# Dev_dsPIC_DIP.net
KiCad netlist of a schematic drawn in EAGLE
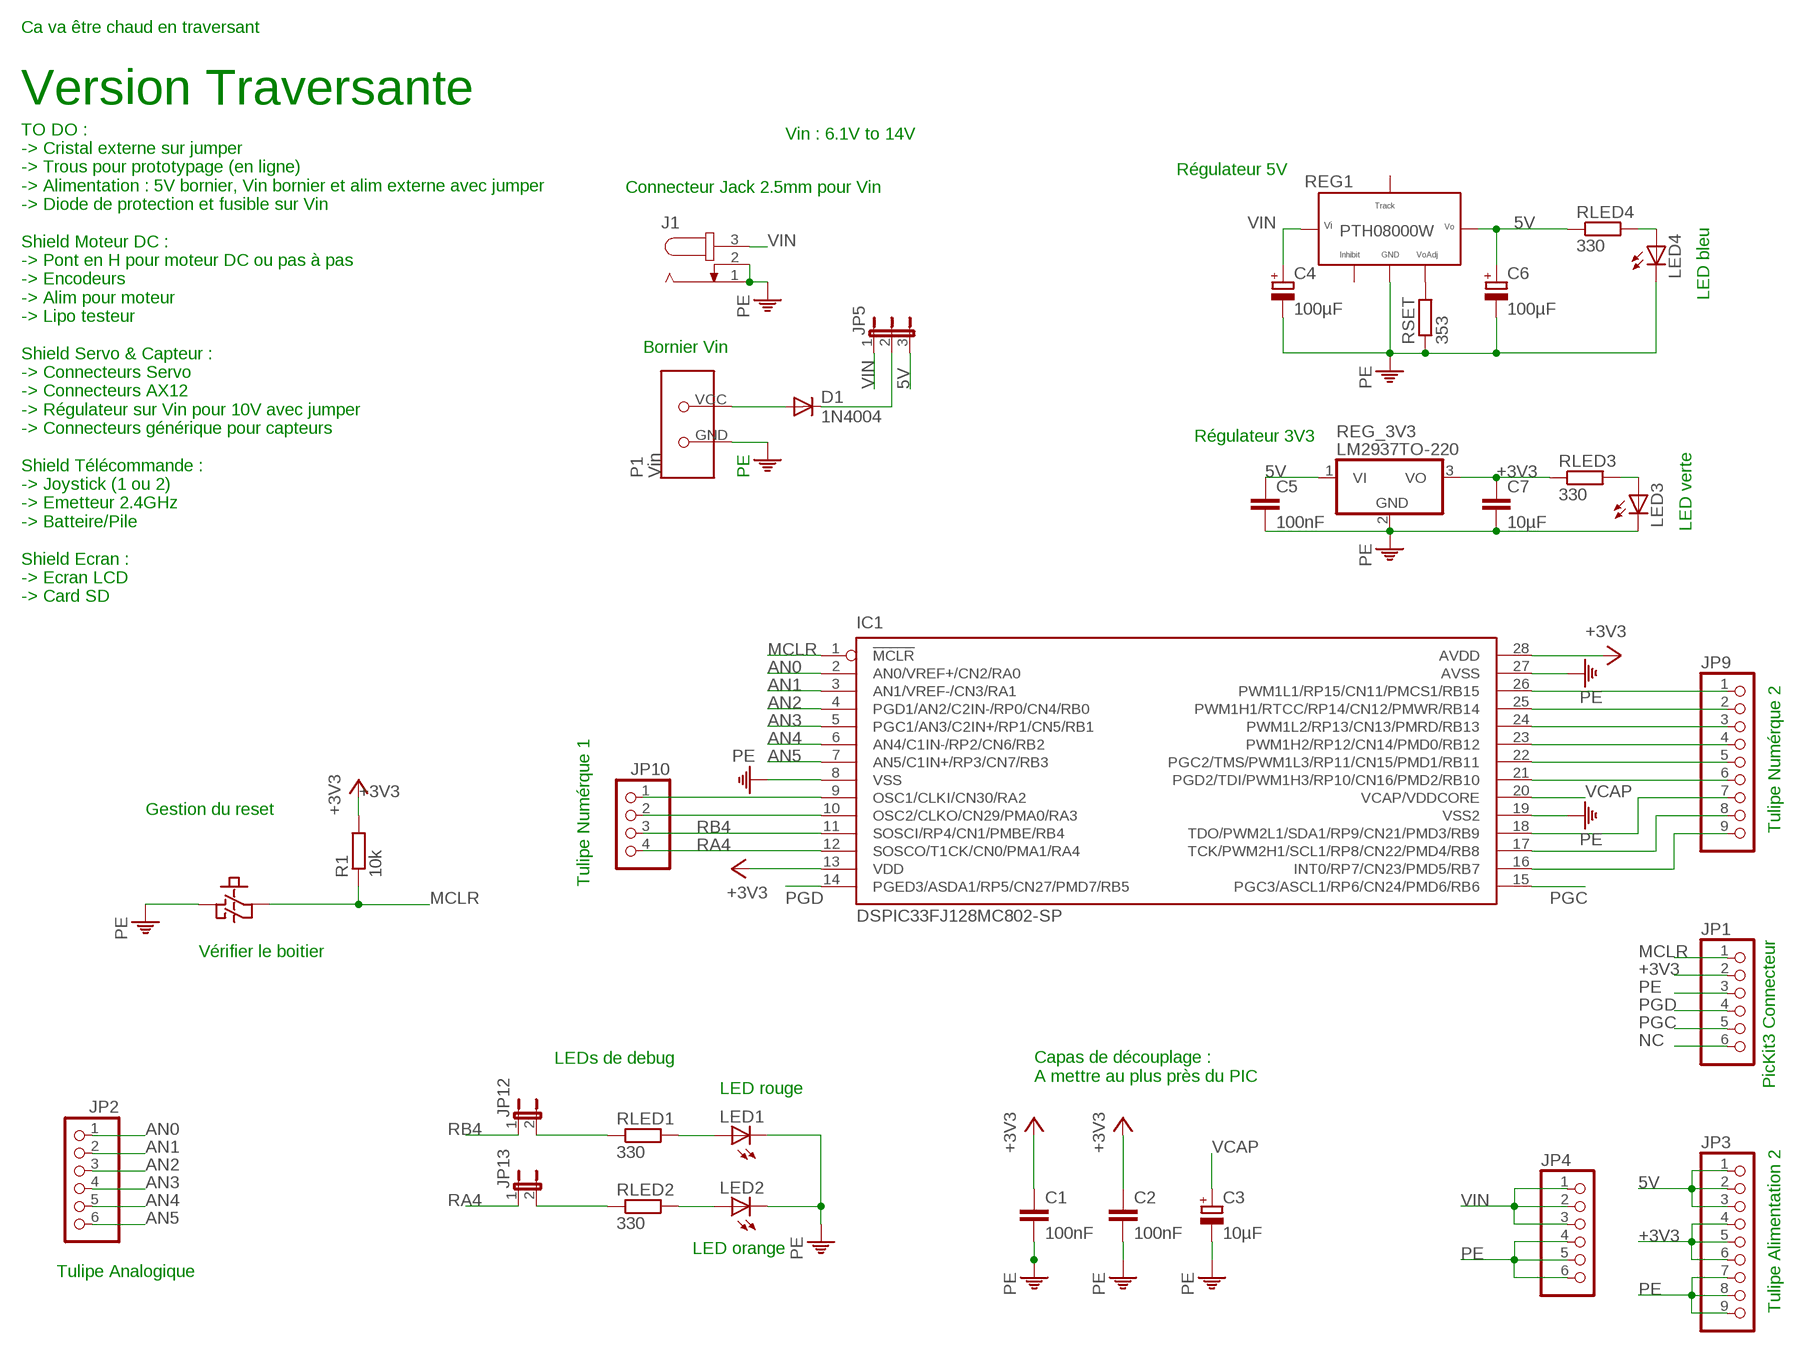
[diagram p0: schematic, sheet 1]

(export (version "E")
  (design (tool "Eeschema 10.0.6"))
  (components
    (comp (ref "C1")
      (value "100nF")
      (footprint "eagle-import:C050-035X075")
      (libsource (lib "eagle-import") (part "C-EU050-035X075"))
    )
    (comp (ref "C2")
      (value "100nF")
      (footprint "eagle-import:C050-035X075")
      (libsource (lib "eagle-import") (part "C-EU050-035X075"))
    )
    (comp (ref "C3")
      (value "10µF")
      (footprint "eagle-import:E2,5-4R")
      (libsource (lib "eagle-import") (part "CPOL-EUE2.5-5V"))
    )
    (comp (ref "C4")
      (value "100µF")
      (footprint "eagle-import:E3,5-8")
      (libsource (lib "eagle-import") (part "CPOL-EUE3.5-8"))
    )
    (comp (ref "C5")
      (value "100nF")
      (footprint "eagle-import:C050-035X075")
      (libsource (lib "eagle-import") (part "C-EU050-035X075"))
    )
    (comp (ref "C6")
      (value "100µF")
      (footprint "eagle-import:E3,5-8")
      (libsource (lib "eagle-import") (part "CPOL-EUE3.5-8"))
    )
    (comp (ref "C7")
      (value "10µF")
      (footprint "eagle-import:C050-035X075")
      (libsource (lib "eagle-import") (part "C-EU050-035X075"))
    )
    (comp (ref "D1")
      (value "1N4004")
      (footprint "eagle-import:DO41-10")
      (libsource (lib "eagle-import") (part "1N4004"))
    )
    (comp (ref "IC1")
      (value "DSPIC33FJ128MC802-SP")
      (footprint "eagle-import:DIL28-3")
      (libsource (lib "eagle-import") (part "DSPIC33FJ128MC802-SP"))
    )
    (comp (ref "J1")
      (value "JACK-PLUG1")
      (footprint "eagle-import:SPC4078")
      (libsource (lib "eagle-import") (part "JACK-PLUG1"))
    )
    (comp (ref "JP1")
      (value "PINHD-1X6/90")
      (footprint "eagle-import:1X06_90")
      (libsource (lib "eagle-import") (part "PINHD-1X6/90"))
    )
    (comp (ref "JP2")
      (value "PINHD-1X6")
      (footprint "eagle-import:1X06")
      (libsource (lib "eagle-import") (part "PINHD-1X6"))
    )
    (comp (ref "JP3")
      (value "PINHD-1X9")
      (footprint "eagle-import:1X09")
      (libsource (lib "eagle-import") (part "PINHD-1X9"))
    )
    (comp (ref "JP4")
      (value "PINHD-1X6")
      (footprint "eagle-import:1X06")
      (libsource (lib "eagle-import") (part "PINHD-1X6"))
    )
    (comp (ref "JP5")
      (value "JP2E")
      (footprint "eagle-import:JP2")
      (libsource (lib "eagle-import") (part "JP2E"))
    )
    (comp (ref "JP9")
      (value "PINHD-1X9")
      (footprint "eagle-import:1X09")
      (libsource (lib "eagle-import") (part "PINHD-1X9"))
    )
    (comp (ref "JP10")
      (value "PINHD-1X4")
      (footprint "eagle-import:1X04")
      (libsource (lib "eagle-import") (part "PINHD-1X4"))
    )
    (comp (ref "JP12")
      (value "JP1E")
      (footprint "eagle-import:JP1")
      (libsource (lib "eagle-import") (part "JP1E"))
    )
    (comp (ref "JP13")
      (value "JP1E")
      (footprint "eagle-import:JP1")
      (libsource (lib "eagle-import") (part "JP1E"))
    )
    (comp (ref "LED1")
      (value "LED3MM")
      (footprint "eagle-import:LED3MM")
      (libsource (lib "eagle-import") (part "LED3MM"))
    )
    (comp (ref "LED2")
      (value "LED3MM")
      (footprint "eagle-import:LED3MM")
      (libsource (lib "eagle-import") (part "LED3MM"))
    )
    (comp (ref "LED3")
      (value "LED3MM")
      (footprint "eagle-import:LED3MM")
      (libsource (lib "eagle-import") (part "LED3MM"))
    )
    (comp (ref "LED4")
      (value "LED3MM")
      (footprint "eagle-import:LED3MM")
      (libsource (lib "eagle-import") (part "LED3MM"))
    )
    (comp (ref "P1")
      (value "Vin")
      (footprint "eagle-import:BORNIER_COUDEE_3.5")
      (libsource (lib "eagle-import") (part "BORNIER_3.5MM"))
    )
    (comp (ref "R1")
      (value "10k")
      (footprint "eagle-import:RES_DIP_PERSO")
      (libsource (lib "eagle-import") (part "RES_PERSO"))
    )
    (comp (ref "REG1")
      (value "PTH08000W(EUS)")
      (footprint "eagle-import:TRHOUGH_HOLE_(EUS)")
      (libsource (lib "eagle-import") (part "PTH08000W(EUS)"))
    )
    (comp (ref "REG_3V3")
      (value "LM2937TO-220")
      (footprint "eagle-import:TO220V")
      (libsource (lib "eagle-import") (part "LM2937TO-220"))
    )
    (comp (ref "RLED1")
      (value "330")
      (footprint "eagle-import:RES_DIP_PERSO")
      (libsource (lib "eagle-import") (part "RES_PERSO"))
    )
    (comp (ref "RLED2")
      (value "330")
      (footprint "eagle-import:RES_DIP_PERSO")
      (libsource (lib "eagle-import") (part "RES_PERSO"))
    )
    (comp (ref "RLED3")
      (value "330")
      (footprint "eagle-import:RES_DIP_PERSO")
      (libsource (lib "eagle-import") (part "RES_PERSO"))
    )
    (comp (ref "RLED4")
      (value "330")
      (footprint "eagle-import:RES_DIP_PERSO")
      (libsource (lib "eagle-import") (part "RES_PERSO"))
    )
    (comp (ref "RSET")
      (value "353")
      (footprint "eagle-import:RES_DIP_PERSO")
      (libsource (lib "eagle-import") (part "RES_PERSO"))
    )
    (comp (ref "U$1") (value "BP") (footprint "eagle-import:BP") (libsource (lib "eagle-import") (part "BP")))
  )
  (nets
    (net (code "1") (name "+3V3") (class "Default")
      (node (ref "C1") (pin "1") (pinfunction "1_1") (pintype "passive"))
      (node (ref "C2") (pin "1") (pinfunction "1_1") (pintype "passive"))
      (node (ref "C7") (pin "1") (pinfunction "1_1") (pintype "passive"))
      (node (ref "IC1") (pin "13") (pinfunction "VDD_13") (pintype "power_in"))
      (node (ref "IC1") (pin "28") (pinfunction "AVDD_28") (pintype "power_in"))
      (node (ref "JP1") (pin "2") (pinfunction "2_2") (pintype "passive"))
      (node (ref "JP3") (pin "4") (pinfunction "4_4") (pintype "passive"))
      (node (ref "JP3") (pin "5") (pinfunction "5_5") (pintype "passive"))
      (node (ref "JP3") (pin "6") (pinfunction "6_6") (pintype "passive"))
      (node (ref "R1") (pin "2") (pinfunction "2_2") (pintype "passive"))
      (node (ref "REG_3V3") (pin "3") (pinfunction "VO_3") (pintype "passive"))
      (node (ref "RLED3") (pin "1") (pinfunction "1_1") (pintype "passive"))
    )
    (net (code "2") (name "/5V") (class "Default")
      (node (ref "C5") (pin "1") (pinfunction "1_1") (pintype "passive"))
      (node (ref "C6") (pin "+") (pinfunction "+_+") (pintype "passive"))
      (node (ref "JP3") (pin "1") (pinfunction "1_1") (pintype "passive"))
      (node (ref "JP3") (pin "2") (pinfunction "2_2") (pintype "passive"))
      (node (ref "JP3") (pin "3") (pinfunction "3_3") (pintype "passive"))
      (node (ref "JP5") (pin "3") (pinfunction "3_3") (pintype "passive"))
      (node (ref "REG1") (pin "6") (pinfunction "6_6") (pintype "bidirectional"))
      (node (ref "REG_3V3") (pin "1") (pinfunction "VI_1") (pintype "input"))
      (node (ref "RLED4") (pin "1") (pinfunction "1_1") (pintype "passive"))
    )
    (net (code "3") (name "/AN0") (class "Default")
      (node (ref "IC1") (pin "2") (pinfunction "AN0/VREF+/CN2/RA0_2") (pintype "bidirectional"))
      (node (ref "JP2") (pin "1") (pinfunction "1_1") (pintype "passive"))
    )
    (net (code "4") (name "/AN1") (class "Default")
      (node (ref "IC1") (pin "3") (pinfunction "AN1/VREF-/CN3/RA1_3") (pintype "bidirectional"))
      (node (ref "JP2") (pin "2") (pinfunction "2_2") (pintype "passive"))
    )
    (net (code "5") (name "/AN2") (class "Default")
      (node (ref "IC1") (pin "4") (pinfunction "PGD1/AN2/C2IN-/RP0/CN4/RB0_4") (pintype "bidirectional"))
      (node (ref "JP2") (pin "3") (pinfunction "3_3") (pintype "passive"))
    )
    (net (code "6") (name "/AN3") (class "Default")
      (node (ref "IC1") (pin "5") (pinfunction "PGC1/AN3/C2IN+/RP1/CN5/RB1_5") (pintype "bidirectional"))
      (node (ref "JP2") (pin "4") (pinfunction "4_4") (pintype "passive"))
    )
    (net (code "7") (name "/AN4") (class "Default")
      (node (ref "IC1") (pin "6") (pinfunction "AN4/C1IN-/RP2/CN6/RB2_6") (pintype "bidirectional"))
      (node (ref "JP2") (pin "5") (pinfunction "5_5") (pintype "passive"))
    )
    (net (code "8") (name "/AN5") (class "Default")
      (node (ref "IC1") (pin "7") (pinfunction "AN5/C1IN+/RP3/CN7/RB3_7") (pintype "bidirectional"))
      (node (ref "JP2") (pin "6") (pinfunction "6_6") (pintype "passive"))
    )
    (net (code "9") (name "/MCLR") (class "Default")
      (node (ref "IC1") (pin "1") (pinfunction "~{MCLR}_1") (pintype "input"))
      (node (ref "JP1") (pin "1") (pinfunction "1_1") (pintype "passive"))
      (node (ref "R1") (pin "1") (pinfunction "1_1") (pintype "passive"))
      (node (ref "U$1") (pin "3") (pinfunction "3_3") (pintype "bidirectional"))
      (node (ref "U$1") (pin "4") (pinfunction "3_4") (pintype "bidirectional"))
    )
    (net (code "10") (name "/NC") (class "Default")
      (node (ref "JP1") (pin "6") (pinfunction "6_6") (pintype "passive"))
    )
    (net (code "11") (name "/PGC") (class "Default")
      (node (ref "IC1") (pin "15") (pinfunction "PGC3/ASCL1/RP6/CN24/PMD6/RB6_15") (pintype "bidirectional"))
      (node (ref "JP1") (pin "5") (pinfunction "5_5") (pintype "passive"))
    )
    (net (code "12") (name "/PGD") (class "Default")
      (node (ref "IC1") (pin "14") (pinfunction "PGED3/ASDA1/RP5/CN27/PMD7/RB5_14") (pintype "bidirectional"))
      (node (ref "JP1") (pin "4") (pinfunction "4_4") (pintype "passive"))
    )
    (net (code "13") (name "/RA4") (class "Default")
      (node (ref "IC1") (pin "12") (pinfunction "SOSCO/T1CK/CN0/PMA1/RA4_12") (pintype "bidirectional"))
      (node (ref "JP10") (pin "4") (pinfunction "4_4") (pintype "passive"))
      (node (ref "JP13") (pin "1") (pinfunction "1_1") (pintype "passive"))
    )
    (net (code "14") (name "/RB4") (class "Default")
      (node (ref "IC1") (pin "11") (pinfunction "SOSCI/RP4/CN1/PMBE/RB4_11") (pintype "bidirectional"))
      (node (ref "JP10") (pin "3") (pinfunction "3_3") (pintype "passive"))
      (node (ref "JP12") (pin "1") (pinfunction "1_1") (pintype "passive"))
    )
    (net (code "15") (name "/VCAP") (class "Default")
      (node (ref "C3") (pin "+") (pinfunction "+_+") (pintype "passive"))
      (node (ref "IC1") (pin "20") (pinfunction "VCAP/VDDCORE_20") (pintype "power_in"))
    )
    (net (code "16") (name "/VIN") (class "Default")
      (node (ref "C4") (pin "+") (pinfunction "+_+") (pintype "passive"))
      (node (ref "J1") (pin "3") (pinfunction "3_3") (pintype "passive"))
      (node (ref "JP4") (pin "1") (pinfunction "1_1") (pintype "passive"))
      (node (ref "JP4") (pin "2") (pinfunction "2_2") (pintype "passive"))
      (node (ref "JP4") (pin "3") (pinfunction "3_3") (pintype "passive"))
      (node (ref "JP5") (pin "1") (pinfunction "1_1") (pintype "passive"))
      (node (ref "REG1") (pin "3") (pinfunction "3_3") (pintype "bidirectional"))
    )
    (net (code "17") (name "Net-(D1-PadA)") (class "Default")
      (node (ref "D1") (pin "A") (pinfunction "A_A") (pintype "passive"))
      (node (ref "P1") (pin "VCC") (pinfunction "VCC_VCC") (pintype "bidirectional"))
    )
    (net (code "18") (name "Net-(D1-PadC)") (class "Default")
      (node (ref "D1") (pin "C") (pinfunction "C_C") (pintype "passive"))
      (node (ref "JP5") (pin "2") (pinfunction "2_2") (pintype "passive"))
    )
    (net (code "19") (name "Net-(IC1-INT0{slash}RP7{slash}CN23{slash}PMD5{slash}RB7)") (class "Default")
      (node (ref "IC1") (pin "16") (pinfunction "INT0/RP7/CN23/PMD5/RB7_16") (pintype "bidirectional"))
      (node (ref "JP9") (pin "9") (pinfunction "9_9") (pintype "passive"))
    )
    (net (code "20") (name "Net-(IC1-OSC1{slash}CLKI{slash}CN30{slash}RA2)") (class "Default")
      (node (ref "IC1") (pin "9") (pinfunction "OSC1/CLKI/CN30/RA2_9") (pintype "bidirectional"))
      (node (ref "JP10") (pin "1") (pinfunction "1_1") (pintype "passive"))
    )
    (net (code "21") (name "Net-(IC1-OSC2{slash}CLKO{slash}CN29{slash}PMA0{slash}RA3)") (class "Default")
      (node (ref "IC1") (pin "10") (pinfunction "OSC2/CLKO/CN29/PMA0/RA3_10") (pintype "bidirectional"))
      (node (ref "JP10") (pin "2") (pinfunction "2_2") (pintype "passive"))
    )
    (net (code "22") (name "Net-(IC1-PGC2{slash}TMS{slash}PWM1L3{slash}RP11{slash}CN15{slash}PMD1{slash}RB11)") (class "Default")
      (node (ref "IC1") (pin "22") (pinfunction "PGC2/TMS/PWM1L3/RP11/CN15/PMD1/RB11_22") (pintype "bidirectional"))
      (node (ref "JP9") (pin "5") (pinfunction "5_5") (pintype "passive"))
    )
    (net (code "23") (name "Net-(IC1-PGD2{slash}TDI{slash}PWM1H3{slash}RP10{slash}CN16{slash}PMD2{slash}RB10)") (class "Default")
      (node (ref "IC1") (pin "21") (pinfunction "PGD2/TDI/PWM1H3/RP10/CN16/PMD2/RB10_21") (pintype "bidirectional"))
      (node (ref "JP9") (pin "6") (pinfunction "6_6") (pintype "passive"))
    )
    (net (code "24") (name "Net-(IC1-PWM1H1{slash}RTCC{slash}RP14{slash}CN12{slash}PMWR{slash}RB14)") (class "Default")
      (node (ref "IC1") (pin "25") (pinfunction "PWM1H1/RTCC/RP14/CN12/PMWR/RB14_25") (pintype "bidirectional"))
      (node (ref "JP9") (pin "2") (pinfunction "2_2") (pintype "passive"))
    )
    (net (code "25") (name "Net-(IC1-PWM1H2{slash}RP12{slash}CN14{slash}PMD0{slash}RB12)") (class "Default")
      (node (ref "IC1") (pin "23") (pinfunction "PWM1H2/RP12/CN14/PMD0/RB12_23") (pintype "bidirectional"))
      (node (ref "JP9") (pin "4") (pinfunction "4_4") (pintype "passive"))
    )
    (net (code "26") (name "Net-(IC1-PWM1L1{slash}RP15{slash}CN11{slash}PMCS1{slash}RB15)") (class "Default")
      (node (ref "IC1") (pin "26") (pinfunction "PWM1L1/RP15/CN11/PMCS1/RB15_26") (pintype "bidirectional"))
      (node (ref "JP9") (pin "1") (pinfunction "1_1") (pintype "passive"))
    )
    (net (code "27") (name "Net-(IC1-PWM1L2{slash}RP13{slash}CN13{slash}PMRD{slash}RB13)") (class "Default")
      (node (ref "IC1") (pin "24") (pinfunction "PWM1L2/RP13/CN13/PMRD/RB13_24") (pintype "bidirectional"))
      (node (ref "JP9") (pin "3") (pinfunction "3_3") (pintype "passive"))
    )
    (net (code "28") (name "Net-(IC1-TCK{slash}PWM2H1{slash}SCL1{slash}RP8{slash}CN22{slash}PMD4{slash}RB8)") (class "Default")
      (node (ref "IC1") (pin "17") (pinfunction "TCK/PWM2H1/SCL1/RP8/CN22/PMD4/RB8_17") (pintype "bidirectional"))
      (node (ref "JP9") (pin "8") (pinfunction "8_8") (pintype "passive"))
    )
    (net (code "29") (name "Net-(IC1-TDO{slash}PWM2L1{slash}SDA1{slash}RP9{slash}CN21{slash}PMD3{slash}RB9)") (class "Default")
      (node (ref "IC1") (pin "18") (pinfunction "TDO/PWM2L1/SDA1/RP9/CN21/PMD3/RB9_18") (pintype "bidirectional"))
      (node (ref "JP9") (pin "7") (pinfunction "7_7") (pintype "passive"))
    )
    (net (code "30") (name "Net-(JP12-Pad2)") (class "Default")
      (node (ref "JP12") (pin "2") (pinfunction "2_2") (pintype "passive"))
      (node (ref "RLED1") (pin "1") (pinfunction "1_1") (pintype "passive"))
    )
    (net (code "31") (name "Net-(JP13-Pad2)") (class "Default")
      (node (ref "JP13") (pin "2") (pinfunction "2_2") (pintype "passive"))
      (node (ref "RLED2") (pin "1") (pinfunction "1_1") (pintype "passive"))
    )
    (net (code "32") (name "Net-(LED1-PadA)") (class "Default")
      (node (ref "LED1") (pin "A") (pinfunction "A_A") (pintype "passive"))
      (node (ref "RLED1") (pin "2") (pinfunction "2_2") (pintype "passive"))
    )
    (net (code "33") (name "Net-(LED2-PadA)") (class "Default")
      (node (ref "LED2") (pin "A") (pinfunction "A_A") (pintype "passive"))
      (node (ref "RLED2") (pin "2") (pinfunction "2_2") (pintype "passive"))
    )
    (net (code "34") (name "Net-(LED3-PadA)") (class "Default")
      (node (ref "LED3") (pin "A") (pinfunction "A_A") (pintype "passive"))
      (node (ref "RLED3") (pin "2") (pinfunction "2_2") (pintype "passive"))
    )
    (net (code "35") (name "Net-(LED4-PadA)") (class "Default")
      (node (ref "LED4") (pin "A") (pinfunction "A_A") (pintype "passive"))
      (node (ref "RLED4") (pin "2") (pinfunction "2_2") (pintype "passive"))
    )
    (net (code "36") (name "Net-(REG1-Pad5)") (class "Default")
      (node (ref "REG1") (pin "5") (pinfunction "5_5") (pintype "bidirectional"))
      (node (ref "RSET") (pin "2") (pinfunction "2_2") (pintype "passive"))
    )
    (net (code "37") (name "PE") (class "Default")
      (node (ref "C1") (pin "2") (pinfunction "2_2") (pintype "passive"))
      (node (ref "C2") (pin "2") (pinfunction "2_2") (pintype "passive"))
      (node (ref "C3") (pin "-") (pinfunction "-_-") (pintype "passive"))
      (node (ref "C4") (pin "-") (pinfunction "-_-") (pintype "passive"))
      (node (ref "C5") (pin "2") (pinfunction "2_2") (pintype "passive"))
      (node (ref "C6") (pin "-") (pinfunction "-_-") (pintype "passive"))
      (node (ref "C7") (pin "2") (pinfunction "2_2") (pintype "passive"))
      (node (ref "IC1") (pin "19") (pinfunction "VSS2_19") (pintype "power_in"))
      (node (ref "IC1") (pin "27") (pinfunction "AVSS_27") (pintype "power_in"))
      (node (ref "IC1") (pin "8") (pinfunction "VSS_8") (pintype "power_in"))
      (node (ref "J1") (pin "1") (pinfunction "1_1") (pintype "passive"))
      (node (ref "J1") (pin "2") (pinfunction "2_2") (pintype "passive"))
      (node (ref "JP1") (pin "3") (pinfunction "3_3") (pintype "passive"))
      (node (ref "JP3") (pin "7") (pinfunction "7_7") (pintype "passive"))
      (node (ref "JP3") (pin "8") (pinfunction "8_8") (pintype "passive"))
      (node (ref "JP3") (pin "9") (pinfunction "9_9") (pintype "passive"))
      (node (ref "JP4") (pin "4") (pinfunction "4_4") (pintype "passive"))
      (node (ref "JP4") (pin "5") (pinfunction "5_5") (pintype "passive"))
      (node (ref "JP4") (pin "6") (pinfunction "6_6") (pintype "passive"))
      (node (ref "LED1") (pin "K") (pinfunction "C_K") (pintype "passive"))
      (node (ref "LED2") (pin "K") (pinfunction "C_K") (pintype "passive"))
      (node (ref "LED3") (pin "K") (pinfunction "C_K") (pintype "passive"))
      (node (ref "LED4") (pin "K") (pinfunction "C_K") (pintype "passive"))
      (node (ref "P1") (pin "GND") (pinfunction "GND_GND") (pintype "bidirectional"))
      (node (ref "REG1") (pin "1") (pinfunction "1_1") (pintype "bidirectional"))
      (node (ref "REG_3V3") (pin "2") (pinfunction "GND_2") (pintype "passive"))
      (node (ref "RSET") (pin "1") (pinfunction "1_1") (pintype "passive"))
      (node (ref "U$1") (pin "1") (pinfunction "1_1") (pintype "bidirectional"))
      (node (ref "U$1") (pin "2") (pinfunction "1_2") (pintype "bidirectional"))
    )
    (net (code "38") (name "unconnected-(REG1-Pad2)") (class "Default")
      (node (ref "REG1") (pin "2") (pinfunction "2_2") (pintype "bidirectional"))
    )
    (net (code "39") (name "unconnected-(REG1-Pad4)") (class "Default")
      (node (ref "REG1") (pin "4") (pinfunction "4_4") (pintype "bidirectional"))
    )
  )
)
